# Intelligent_Agriculture_Power.net
KiCad netlist of a schematic drawn in Altium Designer
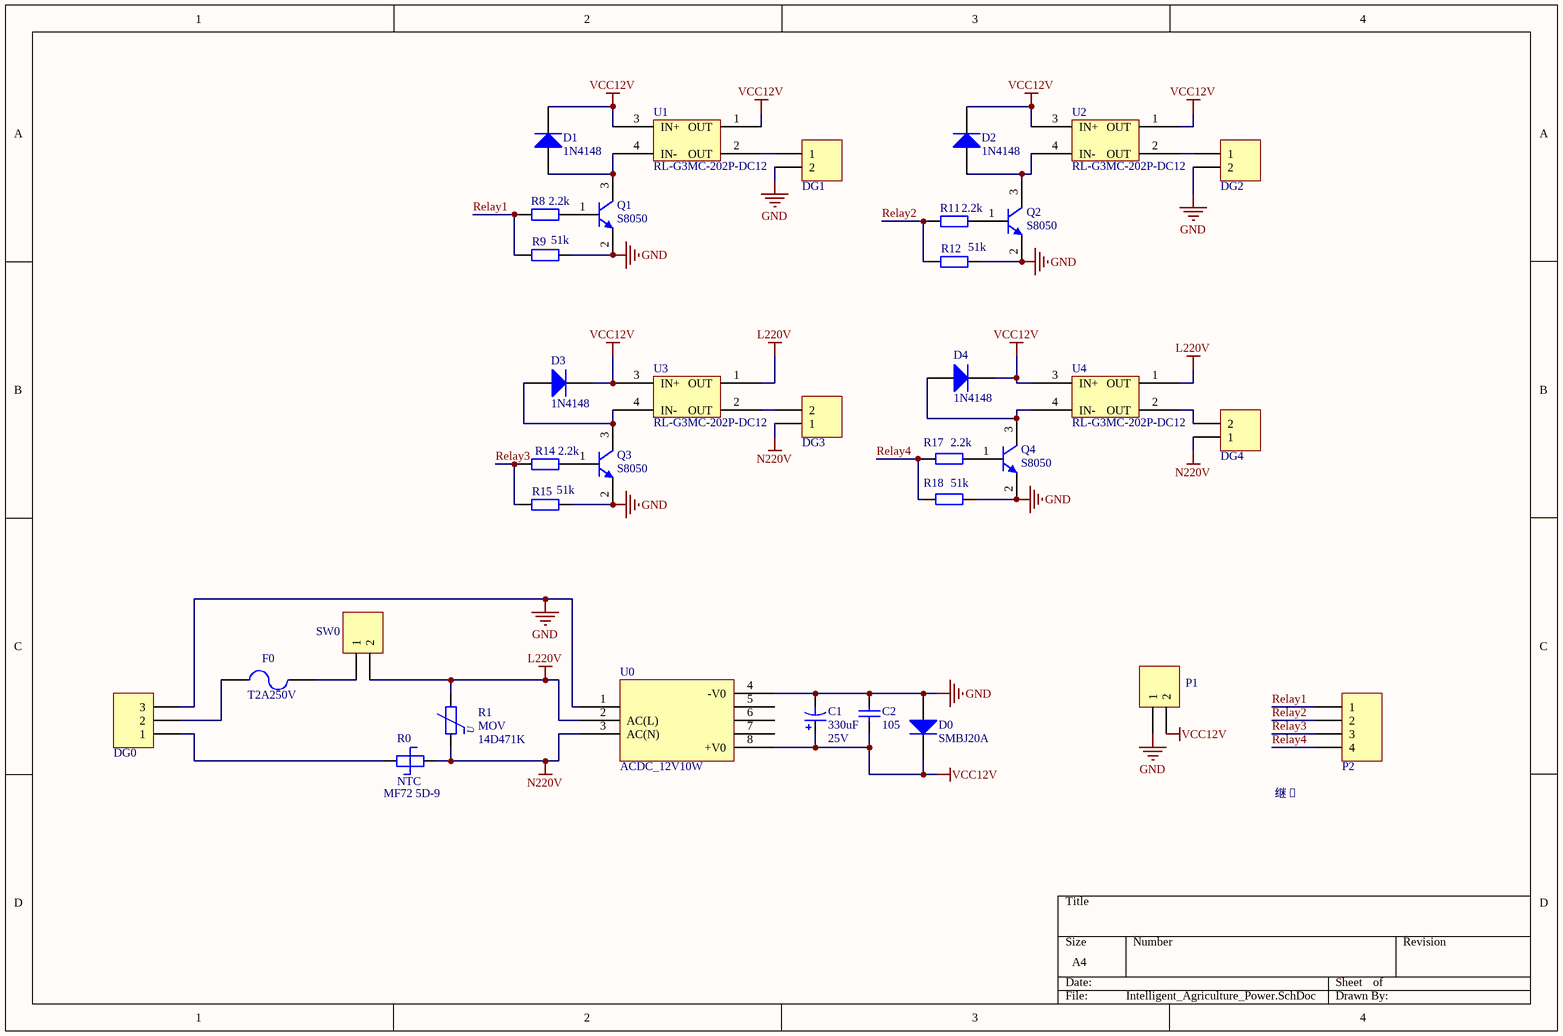
[diagram p0: Intelligent_Agriculture_Power.SchDoc]

(export (version "E")
  (design (tool "Eeschema 10.0.6"))
  (components
    (comp (ref "C1")
      (value "330uF")
      (footprint "C-RB-2.54")
      (description "电解电容")
      (fields
        (field (name "VOL") "25V")
        (field (name "Comment") "Cap Pol1")
        (field (name "PUBLISHER") "Altium Limited")
      )
      (libsource (lib "Miscellaneous Devices") (part "Cap Pol1"))
    )
    (comp (ref "C2")
      (value "105")
      (footprint "C-RAD-0805")
      (description "无极性电容")
      (fields (field (name "Comment") "Cap") (field (name "PUBLISHER") "Altium Limited"))
      (libsource (lib "Intelligent_Agriculture_Lib") (part "Cap"))
    )
    (comp (ref "D0")
      (value "SMBJ20A")
      (footprint "DIODE-1206")
      (description "二极管")
      (fields (field (name "Comment") "Diode") (field (name "PUBLISHER") "Altium Limited"))
      (libsource (lib "Intelligent_Agriculture_Lib") (part "Diode"))
    )
    (comp (ref "D1")
      (value "1N4148")
      (footprint "DIODE-1206")
      (description "二极管")
      (fields (field (name "Comment") "Diode") (field (name "PUBLISHER") "Altium Limited"))
      (libsource (lib "Intelligent_Agriculture_Lib") (part "Diode"))
    )
    (comp (ref "D2")
      (value "1N4148")
      (footprint "DIODE-1206")
      (description "二极管")
      (fields (field (name "Comment") "Diode") (field (name "PUBLISHER") "Altium Limited"))
      (libsource (lib "Intelligent_Agriculture_Lib") (part "Diode"))
    )
    (comp (ref "D3")
      (value "1N4148")
      (footprint "DIODE-1206")
      (description "二极管")
      (fields (field (name "Comment") "Diode") (field (name "PUBLISHER") "Altium Limited"))
      (libsource (lib "Intelligent_Agriculture_Lib") (part "Diode"))
    )
    (comp (ref "D4")
      (value "1N4148")
      (footprint "DIODE-1206")
      (description "二极管")
      (fields (field (name "Comment") "Diode") (field (name "PUBLISHER") "Altium Limited"))
      (libsource (lib "Intelligent_Agriculture_Lib") (part "Diode"))
    )
    (comp (ref "DG0")
      (value "Header 3")
      (footprint "DG301-3P")
      (description "接插件")
      (fields (field (name "PUBLISHER") "Altium Limited"))
      (libsource (lib "Intelligent_Agriculture_Lib") (part "Header 3"))
    )
    (comp (ref "DG1")
      (value "Header 2")
      (description "接插件")
      (fields (field (name "PUBLISHER") "Altium Limited"))
      (libsource (lib "") (part "Header 2_1"))
    )
    (comp (ref "DG2")
      (value "Header 2")
      (description "接插件")
      (fields (field (name "PUBLISHER") "Altium Limited"))
      (libsource (lib "") (part "Header 2_1"))
    )
    (comp (ref "DG3")
      (value "Header 2")
      (description "接插件")
      (fields (field (name "PUBLISHER") "Altium Limited"))
      (libsource (lib "fszhang") (part "Header 2"))
    )
    (comp (ref "DG4")
      (value "Header 2")
      (description "接插件")
      (fields (field (name "PUBLISHER") "Altium Limited"))
      (libsource (lib "fszhang") (part "Header 2"))
    )
    (comp (ref "F0")
      (value "T2A250V")
      (description "保险丝")
      (fields (field (name "Comment") "Fuse") (field (name "PUBLISHER") "Altium Limited"))
      (libsource (lib "fszhang") (part "Fuse 2"))
    )
    (comp (ref "P1")
      (value "Header 2")
      (footprint "HDR2X1_B1")
      (description "接插件")
      (fields (field (name "PUBLISHER") "Altium Limited"))
      (libsource (lib "fszhang") (part "Header 2"))
    )
    (comp (ref "P2")
      (value "Header 4")
      (footprint "HDR4X1_B1")
      (description "接插件")
      (fields (field (name "PUBLISHER") "Altium Limited"))
      (libsource (lib "fszhang") (part "Header 4"))
    )
    (comp (ref "Q1")
      (value "S8050")
      (footprint "SOT-23")
      (description "NPN三极管")
      (fields (field (name "PUBLISHER") "Altium Limited"))
      (libsource (lib "fszhang") (part "BCP68"))
    )
    (comp (ref "Q2")
      (value "S8050")
      (description "NPN三极管")
      (fields (field (name "PUBLISHER") "Altium Limited"))
      (libsource (lib "fszhang") (part "BCP68"))
    )
    (comp (ref "Q3")
      (value "S8050")
      (description "NPN三极管")
      (fields (field (name "PUBLISHER") "Altium Limited"))
      (libsource (lib "fszhang") (part "BCP68"))
    )
    (comp (ref "Q4")
      (value "S8050")
      (description "NPN三极管")
      (fields (field (name "PUBLISHER") "Altium Limited"))
      (libsource (lib "fszhang") (part "BCP68"))
    )
    (comp (ref "R0")
      (value "NTC")
      (description "热敏电阻")
      (fields (field (name "ALTIUM_VALUE") "MF72 5D-9") (field (name "PUBLISHER") "Altium Limited"))
      (libsource (lib "fszhang") (part "NTC"))
    )
    (comp (ref "R1")
      (value "MOV")
      (description "压敏电阻")
      (fields (field (name "ALTIUM_VALUE") "14D471K") (field (name "PUBLISHER") "Altium Limited"))
      (libsource (lib "fszhang") (part "MOV"))
    )
    (comp (ref "R8")
      (value "2.2k")
      (description "贴片电阻")
      (fields (field (name "Comment") "Res1") (field (name "PUBLISHER") "Altium Limited"))
      (libsource (lib "fszhang") (part "Res1"))
    )
    (comp (ref "R9")
      (value "51k")
      (description "贴片电阻")
      (fields (field (name "Comment") "Res1") (field (name "PUBLISHER") "Altium Limited"))
      (libsource (lib "") (part "Res1_1"))
    )
    (comp (ref "R11")
      (value "2.2k")
      (description "贴片电阻")
      (fields (field (name "Comment") "Res1") (field (name "PUBLISHER") "Altium Limited"))
      (libsource (lib "fszhang") (part "Res1"))
    )
    (comp (ref "R12")
      (value "51k")
      (description "贴片电阻")
      (fields (field (name "Comment") "Res1") (field (name "PUBLISHER") "Altium Limited"))
      (libsource (lib "") (part "Res1_1"))
    )
    (comp (ref "R14")
      (value "2.2k")
      (description "贴片电阻")
      (fields (field (name "Comment") "Res1") (field (name "PUBLISHER") "Altium Limited"))
      (libsource (lib "fszhang") (part "Res1"))
    )
    (comp (ref "R15")
      (value "51k")
      (description "贴片电阻")
      (fields (field (name "Comment") "Res1") (field (name "PUBLISHER") "Altium Limited"))
      (libsource (lib "") (part "Res1_1"))
    )
    (comp (ref "R17")
      (value "2.2k")
      (description "贴片电阻")
      (fields (field (name "Comment") "Res1") (field (name "PUBLISHER") "Altium Limited"))
      (libsource (lib "fszhang") (part "Res1"))
    )
    (comp (ref "R18")
      (value "51k")
      (description "贴片电阻")
      (fields (field (name "Comment") "Res1") (field (name "PUBLISHER") "Altium Limited"))
      (libsource (lib "") (part "Res1_1"))
    )
    (comp (ref "SW0")
      (value "Header 2")
      (description "接插件")
      (fields (field (name "PUBLISHER") "Altium Limited"))
      (libsource (lib "fszhang") (part "Header 2"))
    )
    (comp (ref "U0")
      (value "ACDC_12V10W")
      (description "ACDC模块_220VAC转12VDC")
      (libsource (lib "fszhang") (part "ACDC_12V10W"))
    )
    (comp (ref "U1")
      (value "RL-G3MC-202P-DC12")
      (footprint "RL-G3MC-202P-DC12")
      (description "12V 固态继电器")
      (libsource (lib "Intelligent_Agriculture_Lib") (part "RL-G3MC-202P-DC12"))
    )
    (comp (ref "U2")
      (value "RL-G3MC-202P-DC12")
      (footprint "RL-G3MC-202P-DC12")
      (description "12V 固态继电器")
      (libsource (lib "Intelligent_Agriculture_Lib") (part "RL-G3MC-202P-DC12"))
    )
    (comp (ref "U3")
      (value "RL-G3MC-202P-DC12")
      (footprint "RL-G3MC-202P-DC12")
      (description "12V 固态继电器")
      (libsource (lib "Intelligent_Agriculture_Lib") (part "RL-G3MC-202P-DC12"))
    )
    (comp (ref "U4")
      (value "RL-G3MC-202P-DC12")
      (footprint "RL-G3MC-202P-DC12")
      (description "12V 固态继电器")
      (libsource (lib "Intelligent_Agriculture_Lib") (part "RL-G3MC-202P-DC12"))
    )
  )
  (nets
    (net (code "1") (name "/Relay1") (class "Default")
      (node (ref "P2") (pin "1") (pinfunction "1_1") (pintype "passive"))
      (node (ref "R8") (pin "2") (pinfunction "2_2") (pintype "passive"))
      (node (ref "R9") (pin "1") (pinfunction "1_1") (pintype "passive"))
    )
    (net (code "2") (name "/Relay2") (class "Default")
      (node (ref "P2") (pin "2") (pinfunction "2_2") (pintype "passive"))
      (node (ref "R11") (pin "2") (pinfunction "2_2") (pintype "passive"))
      (node (ref "R12") (pin "1") (pinfunction "1_1") (pintype "passive"))
    )
    (net (code "3") (name "/Relay3") (class "Default")
      (node (ref "P2") (pin "3") (pinfunction "3_3") (pintype "passive"))
      (node (ref "R14") (pin "2") (pinfunction "2_2") (pintype "passive"))
      (node (ref "R15") (pin "1") (pinfunction "1_1") (pintype "passive"))
    )
    (net (code "4") (name "/Relay4") (class "Default")
      (node (ref "P2") (pin "4") (pinfunction "4_4") (pintype "passive"))
      (node (ref "R17") (pin "2") (pinfunction "2_2") (pintype "passive"))
      (node (ref "R18") (pin "1") (pinfunction "1_1") (pintype "passive"))
    )
    (net (code "5") (name "GND") (class "Default")
      (node (ref "C1") (pin "2") (pinfunction "2_2") (pintype "passive"))
      (node (ref "C2") (pin "2") (pinfunction "2_2") (pintype "passive"))
      (node (ref "D0") (pin "1") (pinfunction "A_1") (pintype "passive"))
      (node (ref "DG0") (pin "3") (pinfunction "3_3") (pintype "passive"))
      (node (ref "DG1") (pin "2") (pinfunction "2_2") (pintype "passive"))
      (node (ref "DG2") (pin "2") (pinfunction "2_2") (pintype "passive"))
      (node (ref "P1") (pin "1") (pinfunction "1_1") (pintype "passive"))
      (node (ref "Q1") (pin "2") (pinfunction "E_2") (pintype "passive"))
      (node (ref "Q2") (pin "2") (pinfunction "E_2") (pintype "passive"))
      (node (ref "Q3") (pin "2") (pinfunction "E_2") (pintype "passive"))
      (node (ref "Q4") (pin "2") (pinfunction "E_2") (pintype "passive"))
      (node (ref "R12") (pin "2") (pinfunction "2_2") (pintype "passive"))
      (node (ref "R15") (pin "2") (pinfunction "2_2") (pintype "passive"))
      (node (ref "R18") (pin "2") (pinfunction "2_2") (pintype "passive"))
      (node (ref "R9") (pin "2") (pinfunction "2_2") (pintype "passive"))
      (node (ref "U0") (pin "1") (pintype "passive"))
      (node (ref "U0") (pin "4") (pinfunction "-V0_4") (pintype "passive"))
    )
    (net (code "6") (name "L220V") (class "Default")
      (node (ref "R1") (pin "2") (pinfunction "2_2") (pintype "passive"))
      (node (ref "SW0") (pin "2") (pinfunction "2_2") (pintype "passive"))
      (node (ref "U0") (pin "2") (pinfunction "AC(L)_2") (pintype "passive"))
      (node (ref "U3") (pin "1") (pinfunction "OUT_1") (pintype "passive"))
      (node (ref "U4") (pin "1") (pinfunction "OUT_1") (pintype "passive"))
    )
    (net (code "7") (name "N220V") (class "Default")
      (node (ref "DG3") (pin "1") (pinfunction "1_1") (pintype "passive"))
      (node (ref "DG4") (pin "1") (pinfunction "1_1") (pintype "passive"))
      (node (ref "R0") (pin "2") (pinfunction "2_2") (pintype "passive"))
      (node (ref "R1") (pin "1") (pinfunction "1_1") (pintype "passive"))
      (node (ref "U0") (pin "3") (pinfunction "AC(N)_3") (pintype "passive"))
    )
    (net (code "8") (name "Net-(D1-A)") (class "Default")
      (node (ref "D1") (pin "1") (pinfunction "A_1") (pintype "passive"))
      (node (ref "Q1") (pin "3") (pinfunction "C_3") (pintype "passive"))
      (node (ref "U1") (pin "4") (pinfunction "IN-_4") (pintype "passive"))
    )
    (net (code "9") (name "Net-(D2-A)") (class "Default")
      (node (ref "D2") (pin "1") (pinfunction "A_1") (pintype "passive"))
      (node (ref "Q2") (pin "3") (pinfunction "C_3") (pintype "passive"))
      (node (ref "U2") (pin "4") (pinfunction "IN-_4") (pintype "passive"))
    )
    (net (code "10") (name "Net-(D3-A)") (class "Default")
      (node (ref "D3") (pin "1") (pinfunction "A_1") (pintype "passive"))
      (node (ref "Q3") (pin "3") (pinfunction "C_3") (pintype "passive"))
      (node (ref "U3") (pin "4") (pinfunction "IN-_4") (pintype "passive"))
    )
    (net (code "11") (name "Net-(D4-A)") (class "Default")
      (node (ref "D4") (pin "1") (pinfunction "A_1") (pintype "passive"))
      (node (ref "Q4") (pin "3") (pinfunction "C_3") (pintype "passive"))
      (node (ref "U4") (pin "4") (pinfunction "IN-_4") (pintype "passive"))
    )
    (net (code "12") (name "Net-(DG0-Pad1)") (class "Default")
      (node (ref "DG0") (pin "1") (pinfunction "1_1") (pintype "passive"))
      (node (ref "R0") (pin "1") (pinfunction "1_1") (pintype "passive"))
    )
    (net (code "13") (name "Net-(DG0-Pad2)") (class "Default")
      (node (ref "DG0") (pin "2") (pinfunction "2_2") (pintype "passive"))
      (node (ref "F0") (pin "1") (pinfunction "1_1") (pintype "passive"))
    )
    (net (code "14") (name "Net-(DG1-Pad1)") (class "Default")
      (node (ref "DG1") (pin "1") (pinfunction "1_1") (pintype "passive"))
      (node (ref "U1") (pin "2") (pinfunction "OUT_2") (pintype "passive"))
    )
    (net (code "15") (name "Net-(DG2-Pad1)") (class "Default")
      (node (ref "DG2") (pin "1") (pinfunction "1_1") (pintype "passive"))
      (node (ref "U2") (pin "2") (pinfunction "OUT_2") (pintype "passive"))
    )
    (net (code "16") (name "Net-(DG3-Pad2)") (class "Default")
      (node (ref "DG3") (pin "2") (pinfunction "2_2") (pintype "passive"))
      (node (ref "U3") (pin "2") (pinfunction "OUT_2") (pintype "passive"))
    )
    (net (code "17") (name "Net-(DG4-Pad2)") (class "Default")
      (node (ref "DG4") (pin "2") (pinfunction "2_2") (pintype "passive"))
      (node (ref "U4") (pin "2") (pinfunction "OUT_2") (pintype "passive"))
    )
    (net (code "18") (name "Net-(F0-Pad2)") (class "Default")
      (node (ref "F0") (pin "2") (pinfunction "2_2") (pintype "passive"))
      (node (ref "SW0") (pin "1") (pinfunction "1_1") (pintype "passive"))
    )
    (net (code "19") (name "Net-(Q1-B)") (class "Default")
      (node (ref "Q1") (pin "1") (pinfunction "B_1") (pintype "passive"))
      (node (ref "R8") (pin "1") (pinfunction "1_1") (pintype "passive"))
    )
    (net (code "20") (name "Net-(Q2-B)") (class "Default")
      (node (ref "Q2") (pin "1") (pinfunction "B_1") (pintype "passive"))
      (node (ref "R11") (pin "1") (pinfunction "1_1") (pintype "passive"))
    )
    (net (code "21") (name "Net-(Q3-B)") (class "Default")
      (node (ref "Q3") (pin "1") (pinfunction "B_1") (pintype "passive"))
      (node (ref "R14") (pin "1") (pinfunction "1_1") (pintype "passive"))
    )
    (net (code "22") (name "Net-(Q4-B)") (class "Default")
      (node (ref "Q4") (pin "1") (pinfunction "B_1") (pintype "passive"))
      (node (ref "R17") (pin "1") (pinfunction "1_1") (pintype "passive"))
    )
    (net (code "23") (name "VCC12V") (class "Default")
      (node (ref "C1") (pin "1") (pinfunction "1_1") (pintype "passive"))
      (node (ref "C2") (pin "1") (pinfunction "1_1") (pintype "passive"))
      (node (ref "D0") (pin "2") (pinfunction "K_2") (pintype "passive"))
      (node (ref "D1") (pin "2") (pinfunction "K_2") (pintype "passive"))
      (node (ref "D2") (pin "2") (pinfunction "K_2") (pintype "passive"))
      (node (ref "D3") (pin "2") (pinfunction "K_2") (pintype "passive"))
      (node (ref "D4") (pin "2") (pinfunction "K_2") (pintype "passive"))
      (node (ref "P1") (pin "2") (pinfunction "2_2") (pintype "passive"))
      (node (ref "U0") (pin "8") (pinfunction "+V0_8") (pintype "passive"))
      (node (ref "U1") (pin "1") (pinfunction "OUT_1") (pintype "passive"))
      (node (ref "U1") (pin "3") (pinfunction "IN+_3") (pintype "passive"))
      (node (ref "U2") (pin "1") (pinfunction "OUT_1") (pintype "passive"))
      (node (ref "U2") (pin "3") (pinfunction "IN+_3") (pintype "passive"))
      (node (ref "U3") (pin "3") (pinfunction "IN+_3") (pintype "passive"))
      (node (ref "U4") (pin "3") (pinfunction "IN+_3") (pintype "passive"))
    )
    (net (code "24") (name "unconnected-(U0-Pad5)") (class "Default")
      (node (ref "U0") (pin "5") (pintype "passive"))
    )
    (net (code "25") (name "unconnected-(U0-Pad6)") (class "Default")
      (node (ref "U0") (pin "6") (pintype "passive"))
    )
    (net (code "26") (name "unconnected-(U0-Pad7)") (class "Default")
      (node (ref "U0") (pin "7") (pintype "passive"))
    )
  )
)
